# ADR1399_BURN-IN_TOOL.net
KiCad netlist of a schematic drawn in Altium Designer
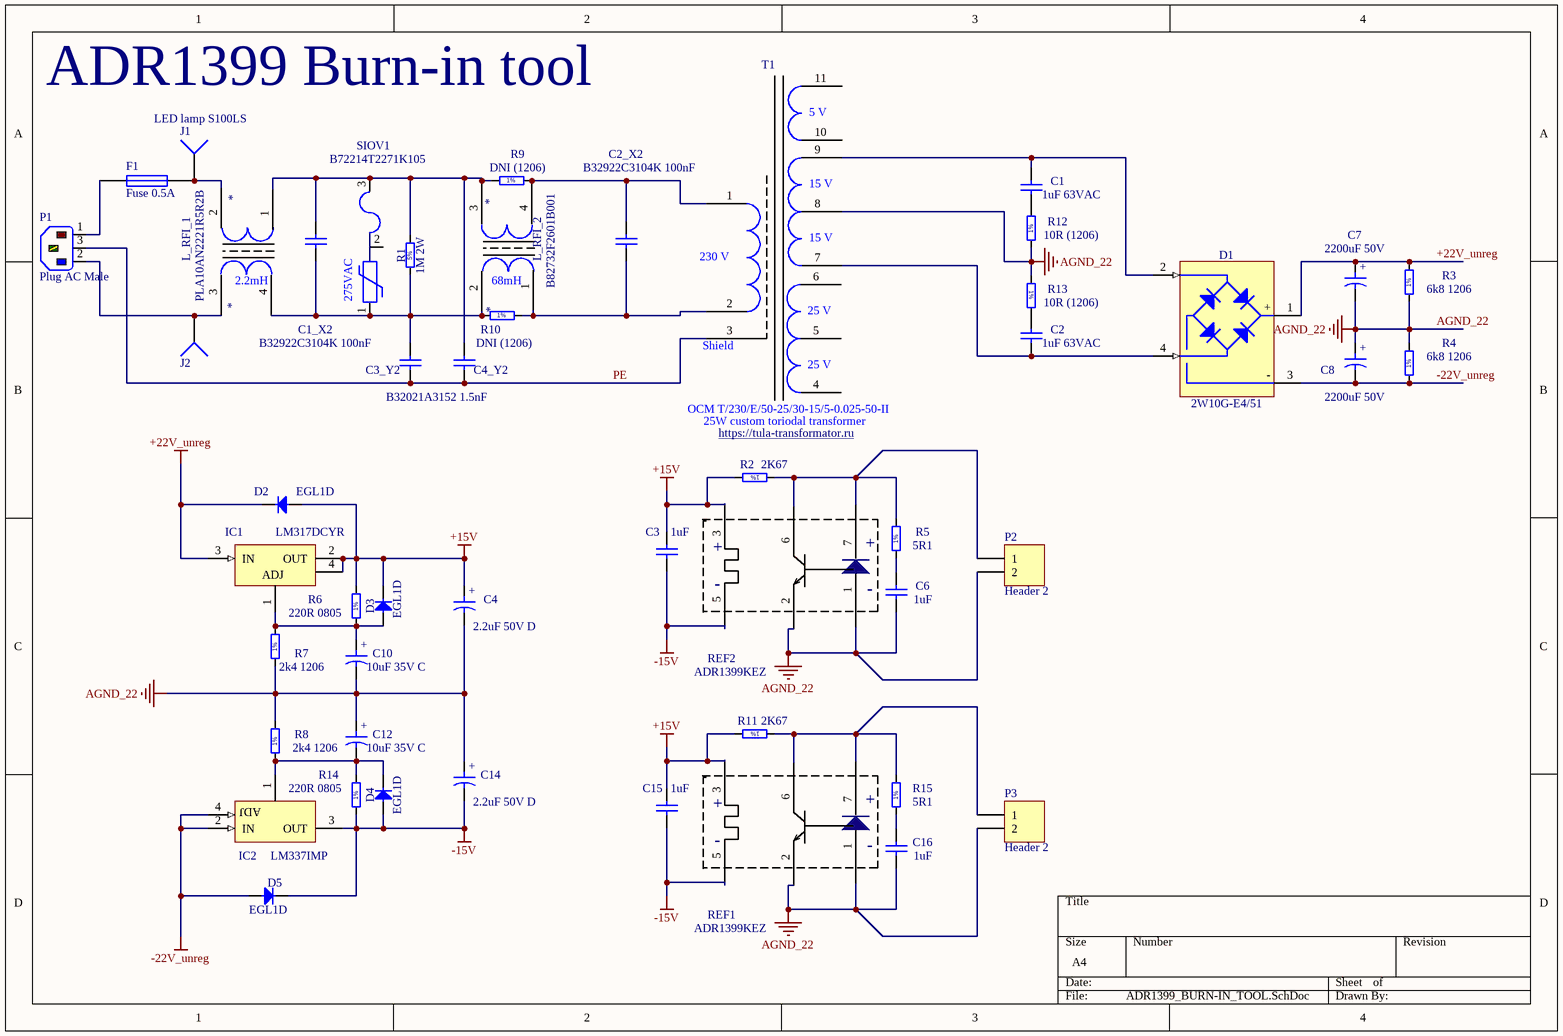
[diagram p0: ADR1399_BURN-IN_TOOL.SchDoc]

(export (version "E")
  (design (tool "Eeschema 10.0.6"))
  (components
    (comp (ref "C1")
      (value "1uF 63VAC")
      (footprint "B32522C1105")
      (description "Non-polarised capacitor")
      (fields
        (field (name "PART NUMBER") "CPPR_330NF_630V_5%_2250-1050X2650X1650")
        (field (name "VOLTAGE") "630VDC/250VAC")
        (field (name "AUTHOR") "CERN DEM JLC")
      )
      (libsource (lib "Capacitors") (part "Capacitor - non polarized"))
    )
    (comp (ref "C1_X2")
      (value "B32922C3104K 100nF")
      (footprint "B32922D3334K")
      (description "Non-polarised capacitor")
      (fields
        (field (name "PART NUMBER") "CPPR_330NF_630V_5%_2250-1050X2650X1650")
        (field (name "VOLTAGE") "630VDC/250VAC")
        (field (name "AUTHOR") "CERN DEM JLC")
      )
      (libsource (lib "Capacitors") (part "Capacitor - non polarized"))
    )
    (comp (ref "C2")
      (value "1uF 63VAC")
      (footprint "B32522C1105")
      (description "Non-polarised capacitor")
      (fields
        (field (name "PART NUMBER") "CPPR_330NF_630V_5%_2250-1050X2650X1650")
        (field (name "VOLTAGE") "630VDC/250VAC")
        (field (name "AUTHOR") "CERN DEM JLC")
      )
      (libsource (lib "Capacitors") (part "Capacitor - non polarized"))
    )
    (comp (ref "C2_X2")
      (value "B32922C3104K 100nF")
      (footprint "B32922D3334K")
      (description "Non-polarised capacitor")
      (fields
        (field (name "PART NUMBER") "CPPR_330NF_630V_5%_2250-1050X2650X1650")
        (field (name "VOLTAGE") "630VDC/250VAC")
        (field (name "AUTHOR") "CERN DEM JLC")
      )
      (libsource (lib "Capacitors") (part "Capacitor - non polarized"))
    )
    (comp (ref "C3")
      (value "1uF")
      (footprint "C0805(2013)")
      (description "Non-polarised capacitor")
      (fields
        (field (name "PART NUMBER") "CC1206_1UF_25V_10%_X7R")
        (field (name "VOLTAGE") "25V")
        (field (name "AUTHOR") "CERN DEM JLC")
      )
      (libsource (lib "Capacitors") (part "Capacitor - non polarized"))
    )
    (comp (ref "C3_Y2")
      (value "B32021A3152 1.5nF")
      (footprint "B32021A3152")
      (description "Non-polarised capacitor")
      (fields
        (field (name "PART NUMBER") "CPPR_330NF_630V_5%_2250-1050X2650X1650")
        (field (name "VOLTAGE") "630VDC/250VAC")
        (field (name "AUTHOR") "CERN DEM JLC")
      )
      (libsource (lib "Capacitors") (part "Capacitor - non polarized"))
    )
    (comp (ref "C4")
      (value "2.2uF 50V D")
      (footprint "CAPMP7343X310N")
      (description "Polarised capacitor")
      (fields
        (field (name "PART NUMBER") "CTE7343-31_22UF_35V_20%_LESR0400")
        (field (name "VOLTAGE") "35V")
        (field (name "AUTHOR") "CERN DEM MR")
      )
      (libsource (lib "Capacitors") (part "Capacitor - polarized"))
    )
    (comp (ref "C4_Y2")
      (value "B32021A3152 1.5nF")
      (footprint "B32021A3152")
      (description "Non-polarised capacitor")
      (fields
        (field (name "PART NUMBER") "CPPR_330NF_630V_5%_2250-1050X2650X1650")
        (field (name "VOLTAGE") "630VDC/250VAC")
        (field (name "AUTHOR") "CERN DEM JLC")
      )
      (libsource (lib "Capacitors") (part "Capacitor - non polarized"))
    )
    (comp (ref "C6")
      (value "1uF")
      (footprint "C0805(2013)")
      (description "Non-polarised capacitor")
      (fields
        (field (name "PART NUMBER") "CC1206_1UF_25V_10%_X7R")
        (field (name "VOLTAGE") "25V")
        (field (name "AUTHOR") "CERN DEM JLC")
      )
      (libsource (lib "Capacitors") (part "Capacitor - non polarized"))
    )
    (comp (ref "C7")
      (value "2200uF 50V")
      (footprint "CAPPR750-1850X3750")
      (description "Polarised capacitor")
      (fields
        (field (name "PART NUMBER") "CAER_10000UF_16V_20%_CHEMI-CON_EKYB160ELL103MMP1S")
        (field (name "VOLTAGE") "16V")
        (field (name "AUTHOR") "CERN DEM JLC")
      )
      (libsource (lib "Capacitors") (part "Capacitor - polarized"))
    )
    (comp (ref "C8")
      (value "2200uF 50V")
      (footprint "CAPPR750-1850X3750")
      (description "Polarised capacitor")
      (fields
        (field (name "PART NUMBER") "CAER_10000UF_16V_20%_CHEMI-CON_EKYB160ELL103MMP1S")
        (field (name "VOLTAGE") "16V")
        (field (name "AUTHOR") "CERN DEM JLC")
      )
      (libsource (lib "Capacitors") (part "Capacitor - polarized"))
    )
    (comp (ref "C10")
      (value "10uF 35V C")
      (footprint "CAPMP6032X280N")
      (description "Polarised capacitor")
      (fields
        (field (name "PART NUMBER") "CTE6032-28_10UF_25V_10%_LESR0500")
        (field (name "VOLTAGE") "25V")
        (field (name "AUTHOR") "CERN DEM JLC")
      )
      (libsource (lib "Capacitors") (part "Capacitor - polarized"))
    )
    (comp (ref "C12")
      (value "10uF 35V C")
      (footprint "CAPMP6032X280N")
      (description "Polarised capacitor")
      (fields
        (field (name "PART NUMBER") "CTE6032-28_10UF_25V_10%_LESR0500")
        (field (name "VOLTAGE") "25V")
        (field (name "AUTHOR") "CERN DEM JLC")
      )
      (libsource (lib "Capacitors") (part "Capacitor - polarized"))
    )
    (comp (ref "C14")
      (value "2.2uF 50V D")
      (footprint "CAPMP7343X310N")
      (description "Polarised capacitor")
      (fields
        (field (name "PART NUMBER") "CTE7343-31_22UF_35V_20%_LESR0400")
        (field (name "VOLTAGE") "35V")
        (field (name "AUTHOR") "CERN DEM MR")
      )
      (libsource (lib "Capacitors") (part "Capacitor - polarized"))
    )
    (comp (ref "C15")
      (value "1uF")
      (footprint "C0805(2013)")
      (description "Non-polarised capacitor")
      (fields
        (field (name "PART NUMBER") "CC1206_1UF_25V_10%_X7R")
        (field (name "VOLTAGE") "25V")
        (field (name "AUTHOR") "CERN DEM JLC")
      )
      (libsource (lib "Capacitors") (part "Capacitor - non polarized"))
    )
    (comp (ref "C16")
      (value "1uF")
      (footprint "C0805(2013)")
      (description "Non-polarised capacitor")
      (fields
        (field (name "PART NUMBER") "CC1206_1UF_25V_10%_X7R")
        (field (name "VOLTAGE") "25V")
        (field (name "AUTHOR") "CERN DEM JLC")
      )
      (libsource (lib "Capacitors") (part "Capacitor - non polarized"))
    )
    (comp (ref "D1")
      (value "2W10G-E4/51")
      (footprint "VISHAY_WOG")
      (description "Bridge Rectifier 1+ 2AC 3- 4AC")
      (fields
        (field (name "PART NUMBER") "W005G-E4/51")
        (field (name "VOLTAGE") "50V")
        (field (name "AUTHOR") "CERN DEM JLC")
      )
      (libsource (lib "ICs And Semiconductors") (part "Bridge Rectifier 1+ 2AC 3- 4AC"))
    )
    (comp (ref "D2")
      (value "EGL1D")
      (footprint "DIOMELF3515N")
      (description "Diode")
      (fields
        (field (name "PART NUMBER") "PMLL4148L")
        (field (name "VOLTAGE") "75V")
        (field (name "AUTHOR") "CERN DEM JLC")
      )
      (libsource (lib "ICs And Semiconductors") (part "Diode"))
    )
    (comp (ref "D3")
      (value "EGL1D")
      (footprint "DIOMELF3515N")
      (description "Diode")
      (fields
        (field (name "PART NUMBER") "PMLL4148L")
        (field (name "VOLTAGE") "75V")
        (field (name "AUTHOR") "CERN DEM JLC")
      )
      (libsource (lib "ICs And Semiconductors") (part "Diode"))
    )
    (comp (ref "D4")
      (value "EGL1D")
      (footprint "DIOMELF3515N")
      (description "Diode")
      (fields
        (field (name "PART NUMBER") "PMLL4148L")
        (field (name "VOLTAGE") "75V")
        (field (name "AUTHOR") "CERN DEM JLC")
      )
      (libsource (lib "ICs And Semiconductors") (part "Diode"))
    )
    (comp (ref "D5")
      (value "EGL1D")
      (footprint "DIOMELF3515N")
      (description "Diode")
      (fields
        (field (name "PART NUMBER") "PMLL4148L")
        (field (name "VOLTAGE") "75V")
        (field (name "AUTHOR") "CERN DEM JLC")
      )
      (libsource (lib "ICs And Semiconductors") (part "Diode"))
    )
    (comp (ref "F1")
      (value "Fuse 0.5A")
      (footprint "FUSE")
      (description "Fuse")
      (fields (field (name "PUBLISHER") "Altium Limited"))
      (libsource (lib "Miscellaneous Devices") (part "Fuse 1"))
    )
    (comp (ref "IC1")
      (value "LM317DCYR")
      (footprint "SOT230P700X180-4N")
      (description "3-Terminal Regulator 1=Adj 2=OUT 3=IN 4=OUT")
      (fields
        (field (name "PART NUMBER") "LM317EMP")
        (field (name "MANUFACTURER") "TEXAS INSTRUMENTS")
        (field (name "AUTHOR") "CERN DEM JLC")
      )
      (libsource (lib "ICs And Semiconductors") (part "REG3+1 1ADJ-2OUT-3IN+4OUT"))
    )
    (comp (ref "IC2")
      (value "LM337IMP")
      (footprint "SOT230P700X180-4N")
      (description "3-Terminal Regulator 1=Adj 2=IN 3=OUT 4=IN")
      (fields
        (field (name "PART NUMBER") "LM337IMP/NOPB")
        (field (name "MANUFACTURER") "TEXAS INSTRUMENTS")
        (field (name "AUTHOR") "CERN DEM JLC")
      )
      (libsource (lib "ICs And Semiconductors") (part "REG3+1 1ADJ-2IN-3OUT+4IN"))
    )
    (comp (ref "J1")
      (value "Socket")
      (footprint "PIN1")
      (fields (field (name "PUBLISHER") "Altium Limited"))
      (libsource (lib "Miscellaneous Connectors") (part "Socket"))
    )
    (comp (ref "J2")
      (value "Socket")
      (footprint "PIN1")
      (fields (field (name "PUBLISHER") "Altium Limited"))
      (libsource (lib "Miscellaneous Connectors") (part "Socket"))
    )
    (comp (ref "L_RFI_1")
      (value "PLA10AN2221R5R2B")
      (footprint "PLA10AN2221R5R2B")
      (libsource (lib "My SCH library") (part "PLA10AN2221R5R2B"))
    )
    (comp (ref "L_RFI_2")
      (value "B82732F2601B001")
      (footprint "B82732F")
      (libsource (lib "") (part "PLA10AN2221R5R2B_1"))
    )
    (comp (ref "P1")
      (value "Plug AC Male")
      (footprint "AS-205")
      (description "IEC Mains Power Inlet, EN60 320-1 C14 Class I Cold Condition, PC Flange Rear Mount, Chassis Plug")
      (fields (field (name "PUBLISHER") "Altium Limited"))
      (libsource (lib "Miscellaneous Connectors") (part "Plug AC Male"))
    )
    (comp (ref "P2")
      (value "Header 2")
      (footprint "HDR1X2")
      (description "Header, 2-Pin")
      (fields (field (name "PUBLISHER") "Altium Limited"))
      (libsource (lib "Miscellaneous Connectors") (part "Header 2"))
    )
    (comp (ref "P3")
      (value "Header 2")
      (footprint "HDR1X2")
      (description "Header, 2-Pin")
      (fields (field (name "PUBLISHER") "Altium Limited"))
      (libsource (lib "Miscellaneous Connectors") (part "Header 2"))
    )
    (comp (ref "R1")
      (value "1M 2W")
      (footprint "RES_TYCO_CFR200")
      (description "Resistor - 5%")
      (fields
        (field (name "PART NUMBER") "RCF_NO-VALUE_5%_2W_0-450PPM_TYCO_CFR200")
        (field (name "POWER") "2W")
        (field (name "AUTHOR") "CERN DEM JLC")
      )
      (libsource (lib "Resistors") (part "Resistor - 5%"))
    )
    (comp (ref "R2")
      (value "2K67")
      (footprint "R0603-1%")
      (description "Resistor - 1%")
      (fields
        (field (name "PART NUMBER") "R1206_5R6_1%_0.25W_200PPM")
        (field (name "POWER") "0.25W")
        (field (name "AUTHOR") "CERN DEM JLC")
      )
      (libsource (lib "Resistors") (part "Resistor - 1%"))
    )
    (comp (ref "R3")
      (value "6k8 1206")
      (footprint "RESC3216X65N")
      (description "Resistor - 1%")
      (fields
        (field (name "PART NUMBER") "R1206_2K4_1%_0.25W_100PPM")
        (field (name "POWER") "0.25W")
        (field (name "AUTHOR") "CERN DEM JLC")
      )
      (libsource (lib "Resistors") (part "Resistor - 1%"))
    )
    (comp (ref "R4")
      (value "6k8 1206")
      (footprint "RESC3216X65N")
      (description "Resistor - 1%")
      (fields
        (field (name "PART NUMBER") "R1206_2K4_1%_0.25W_100PPM")
        (field (name "POWER") "0.25W")
        (field (name "AUTHOR") "CERN DEM JLC")
      )
      (libsource (lib "Resistors") (part "Resistor - 1%"))
    )
    (comp (ref "R5")
      (value "5R1")
      (footprint "R0603-1%")
      (description "Resistor - 1%")
      (fields
        (field (name "PART NUMBER") "R1206_5R6_1%_0.25W_200PPM")
        (field (name "POWER") "0.25W")
        (field (name "AUTHOR") "CERN DEM JLC")
      )
      (libsource (lib "Resistors") (part "Resistor - 1%"))
    )
    (comp (ref "R6")
      (value "220R 0805")
      (footprint "RESC2012X60N")
      (description "Resistor - 1%")
      (fields
        (field (name "PART NUMBER") "R0805_220R_1%_0.125W_100PPM")
        (field (name "POWER") "0.125W")
        (field (name "AUTHOR") "CERN DEM JLC")
      )
      (libsource (lib "Resistors") (part "Resistor - 1%"))
    )
    (comp (ref "R7")
      (value "2k4 1206")
      (footprint "RESC3216X65N")
      (description "Resistor - 1%")
      (fields
        (field (name "PART NUMBER") "R1206_2K4_1%_0.25W_100PPM")
        (field (name "POWER") "0.25W")
        (field (name "AUTHOR") "CERN DEM JLC")
      )
      (libsource (lib "Resistors") (part "Resistor - 1%"))
    )
    (comp (ref "R8")
      (value "2k4 1206")
      (footprint "RESC3216X65N")
      (description "Resistor - 1%")
      (fields
        (field (name "PART NUMBER") "R1206_2K4_1%_0.25W_100PPM")
        (field (name "POWER") "0.25W")
        (field (name "AUTHOR") "CERN DEM JLC")
      )
      (libsource (lib "Resistors") (part "Resistor - 1%"))
    )
    (comp (ref "R9")
      (value "DNI (1206)")
      (footprint "RESC3216X65N")
      (description "Resistor - 1%")
      (fields
        (field (name "PART NUMBER") "R1206_2K4_1%_0.25W_100PPM")
        (field (name "POWER") "0.25W")
        (field (name "AUTHOR") "CERN DEM JLC")
      )
      (libsource (lib "Resistors") (part "Resistor - 1%"))
    )
    (comp (ref "R10")
      (value "DNI (1206)")
      (footprint "RESC3216X65N")
      (description "Resistor - 1%")
      (fields
        (field (name "PART NUMBER") "R1206_2K4_1%_0.25W_100PPM")
        (field (name "POWER") "0.25W")
        (field (name "AUTHOR") "CERN DEM JLC")
      )
      (libsource (lib "Resistors") (part "Resistor - 1%"))
    )
    (comp (ref "R11")
      (value "2K67")
      (footprint "R0603-1%")
      (description "Resistor - 1%")
      (fields
        (field (name "PART NUMBER") "R1206_5R6_1%_0.25W_200PPM")
        (field (name "POWER") "0.25W")
        (field (name "AUTHOR") "CERN DEM JLC")
      )
      (libsource (lib "Resistors") (part "Resistor - 1%"))
    )
    (comp (ref "R12")
      (value "10R (1206)")
      (footprint "RESC3216X65N")
      (description "Resistor - 1%")
      (fields
        (field (name "PART NUMBER") "R1206_2K4_1%_0.25W_100PPM")
        (field (name "POWER") "0.25W")
        (field (name "AUTHOR") "CERN DEM JLC")
      )
      (libsource (lib "Resistors") (part "Resistor - 1%"))
    )
    (comp (ref "R13")
      (value "10R (1206)")
      (footprint "RESC3216X65N")
      (description "Resistor - 1%")
      (fields
        (field (name "PART NUMBER") "R1206_2K4_1%_0.25W_100PPM")
        (field (name "POWER") "0.25W")
        (field (name "AUTHOR") "CERN DEM JLC")
      )
      (libsource (lib "Resistors") (part "Resistor - 1%"))
    )
    (comp (ref "R14")
      (value "220R 0805")
      (footprint "RESC2012X60N")
      (description "Resistor - 1%")
      (fields
        (field (name "PART NUMBER") "R0805_220R_1%_0.125W_100PPM")
        (field (name "POWER") "0.125W")
        (field (name "AUTHOR") "CERN DEM JLC")
      )
      (libsource (lib "Resistors") (part "Resistor - 1%"))
    )
    (comp (ref "R15")
      (value "5R1")
      (footprint "R0603-1%")
      (description "Resistor - 1%")
      (fields
        (field (name "PART NUMBER") "R1206_5R6_1%_0.25W_200PPM")
        (field (name "POWER") "0.25W")
        (field (name "AUTHOR") "CERN DEM JLC")
      )
      (libsource (lib "Resistors") (part "Resistor - 1%"))
    )
    (comp (ref "REF1")
      (value "ADR1399KEZ")
      (footprint "LCC-8 socket")
      (libsource (lib "My SCH library") (part "ADR1399KEZ"))
    )
    (comp (ref "REF2")
      (value "ADR1399KEZ")
      (footprint "LCC-8 socket")
      (libsource (lib "My SCH library") (part "ADR1399KEZ"))
    )
    (comp (ref "SIOV1")
      (value "B72214T2271K105")
      (footprint "B72214T2271K105")
      (fields (field (name "ORDER") "B72214T2271K105") (field (name "PUBLISHER") "Altium Limited"))
      (libsource (lib "My SCH library") (part "B72214T2271K105"))
    )
    (comp (ref "T1")
      (value "OCM T/230/E/50-25/30-15/5-0.025-50-II")
      (footprint "OCM T/230/E/50-25/30-15/5-0.025-50-II")
      (libsource (lib "My SCH library") (part "OCM T/230/E/50-25/30-15/5-0.025-50-II"))
    )
  )
  (nets
    (net (code "1") (name "+15V") (class "Default")
      (node (ref "C15") (pin "2") (pinfunction "2_2") (pintype "passive"))
      (node (ref "C3") (pin "2") (pinfunction "2_2") (pintype "passive"))
      (node (ref "C4") (pin "1") (pinfunction "1_1") (pintype "passive"))
      (node (ref "D2") (pin "2") (pinfunction "A_2") (pintype "passive"))
      (node (ref "D3") (pin "1") (pinfunction "C_1") (pintype "passive"))
      (node (ref "IC1") (pin "2") (pinfunction "OUT_2") (pintype "power_in"))
      (node (ref "IC1") (pin "4") (pinfunction "OUT_4") (pintype "power_in"))
      (node (ref "R11") (pin "2") (pinfunction "2_2") (pintype "passive"))
      (node (ref "R2") (pin "2") (pinfunction "2_2") (pintype "passive"))
      (node (ref "R6") (pin "2") (pinfunction "2_2") (pintype "passive"))
      (node (ref "REF1") (pin "3") (pinfunction "3_3") (pintype "passive"))
      (node (ref "REF2") (pin "3") (pinfunction "3_3") (pintype "passive"))
    )
    (net (code "2") (name "+22V_unreg") (class "Default")
      (node (ref "C7") (pin "1") (pinfunction "1_1") (pintype "passive"))
      (node (ref "D1") (pin "1") (pinfunction "+_1") (pintype "power_in"))
      (node (ref "D2") (pin "1") (pinfunction "C_1") (pintype "passive"))
      (node (ref "IC1") (pin "3") (pinfunction "IN_3") (pintype "input"))
      (node (ref "R3") (pin "2") (pinfunction "2_2") (pintype "passive"))
    )
    (net (code "3") (name "-15V") (class "Default")
      (node (ref "C14") (pin "2") (pinfunction "2_2") (pintype "passive"))
      (node (ref "C15") (pin "1") (pinfunction "1_1") (pintype "passive"))
      (node (ref "C3") (pin "1") (pinfunction "1_1") (pintype "passive"))
      (node (ref "D4") (pin "2") (pinfunction "A_2") (pintype "passive"))
      (node (ref "D5") (pin "1") (pinfunction "C_1") (pintype "passive"))
      (node (ref "IC2") (pin "3") (pinfunction "OUT_3") (pintype "power_in"))
      (node (ref "R14") (pin "1") (pinfunction "1_1") (pintype "passive"))
      (node (ref "REF1") (pin "5") (pinfunction "5_5") (pintype "passive"))
      (node (ref "REF2") (pin "5") (pinfunction "5_5") (pintype "passive"))
    )
    (net (code "4") (name "-22V_unreg") (class "Default")
      (node (ref "C8") (pin "2") (pinfunction "2_2") (pintype "passive"))
      (node (ref "D1") (pin "3") (pinfunction "-_3") (pintype "power_in"))
      (node (ref "D5") (pin "2") (pinfunction "A_2") (pintype "passive"))
      (node (ref "IC2") (pin "2") (pinfunction "IN_2") (pintype "input"))
      (node (ref "IC2") (pin "4") (pinfunction "IN_4") (pintype "input"))
      (node (ref "R4") (pin "1") (pinfunction "1_1") (pintype "passive"))
    )
    (net (code "5") (name "/PE") (class "Default")
      (node (ref "C3_Y2") (pin "1") (pinfunction "1_1") (pintype "passive"))
      (node (ref "C4_Y2") (pin "1") (pinfunction "1_1") (pintype "passive"))
      (node (ref "P1") (pin "3") (pinfunction "E_3") (pintype "power_in"))
      (node (ref "T1") (pin "3") (pinfunction "3_3") (pintype "passive"))
    )
    (net (code "6") (name "AGND_22") (class "Default")
      (node (ref "C10") (pin "2") (pinfunction "2_2") (pintype "passive"))
      (node (ref "C12") (pin "1") (pinfunction "1_1") (pintype "passive"))
      (node (ref "C14") (pin "1") (pinfunction "1_1") (pintype "passive"))
      (node (ref "C16") (pin "1") (pinfunction "1_1") (pintype "passive"))
      (node (ref "C4") (pin "2") (pinfunction "2_2") (pintype "passive"))
      (node (ref "C6") (pin "1") (pinfunction "1_1") (pintype "passive"))
      (node (ref "C7") (pin "2") (pinfunction "2_2") (pintype "passive"))
      (node (ref "C8") (pin "1") (pinfunction "1_1") (pintype "passive"))
      (node (ref "P2") (pin "2") (pinfunction "2_2") (pintype "passive"))
      (node (ref "P3") (pin "2") (pinfunction "2_2") (pintype "passive"))
      (node (ref "R12") (pin "1") (pinfunction "1_1") (pintype "passive"))
      (node (ref "R13") (pin "1") (pinfunction "1_1") (pintype "passive"))
      (node (ref "R3") (pin "1") (pinfunction "1_1") (pintype "passive"))
      (node (ref "R4") (pin "2") (pinfunction "2_2") (pintype "passive"))
      (node (ref "R7") (pin "1") (pinfunction "1_1") (pintype "passive"))
      (node (ref "R8") (pin "2") (pinfunction "2_2") (pintype "passive"))
      (node (ref "REF1") (pin "1") (pinfunction "1_1") (pintype "passive"))
      (node (ref "REF1") (pin "2") (pinfunction "2_2") (pintype "passive"))
      (node (ref "REF2") (pin "1") (pinfunction "1_1") (pintype "passive"))
      (node (ref "REF2") (pin "2") (pinfunction "2_2") (pintype "passive"))
      (node (ref "T1") (pin "8") (pinfunction "8_8") (pintype "passive"))
    )
    (net (code "7") (name "Net-(C1-Pad1)") (class "Default")
      (node (ref "C1") (pin "1") (pinfunction "1_1") (pintype "passive"))
      (node (ref "R12") (pin "2") (pinfunction "2_2") (pintype "passive"))
    )
    (net (code "8") (name "Net-(C1-Pad2)") (class "Default")
      (node (ref "C1") (pin "2") (pinfunction "2_2") (pintype "passive"))
      (node (ref "D1") (pin "2") (pinfunction "AC_2") (pintype "input"))
      (node (ref "T1") (pin "9") (pinfunction "9_9") (pintype "passive"))
    )
    (net (code "9") (name "Net-(C1_X2-Pad1)") (class "Default")
      (node (ref "C1_X2") (pin "1") (pinfunction "1_1") (pintype "passive"))
      (node (ref "C3_Y2") (pin "2") (pinfunction "2_2") (pintype "passive"))
      (node (ref "L_RFI_1") (pin "4") (pinfunction "4_4") (pintype "passive"))
      (node (ref "L_RFI_2") (pin "2") (pinfunction "2_2") (pintype "passive"))
      (node (ref "R1") (pin "1") (pinfunction "1_1") (pintype "passive"))
      (node (ref "R10") (pin "1") (pinfunction "1_1") (pintype "passive"))
      (node (ref "SIOV1") (pin "1") (pinfunction "1_1") (pintype "passive"))
    )
    (net (code "10") (name "Net-(C1_X2-Pad2)") (class "Default")
      (node (ref "C1_X2") (pin "2") (pinfunction "2_2") (pintype "passive"))
      (node (ref "C4_Y2") (pin "2") (pinfunction "2_2") (pintype "passive"))
      (node (ref "L_RFI_1") (pin "1") (pinfunction "1_1") (pintype "passive"))
      (node (ref "L_RFI_2") (pin "3") (pinfunction "3_3") (pintype "passive"))
      (node (ref "R1") (pin "2") (pinfunction "2_2") (pintype "passive"))
      (node (ref "R9") (pin "1") (pinfunction "1_1") (pintype "passive"))
      (node (ref "SIOV1") (pin "3") (pinfunction "3_3") (pintype "passive"))
    )
    (net (code "11") (name "Net-(C2-Pad1)") (class "Default")
      (node (ref "C2") (pin "1") (pinfunction "1_1") (pintype "passive"))
      (node (ref "D1") (pin "4") (pinfunction "AC_4") (pintype "input"))
      (node (ref "T1") (pin "7") (pinfunction "8_7") (pintype "passive"))
    )
    (net (code "12") (name "Net-(C2-Pad2)") (class "Default")
      (node (ref "C2") (pin "2") (pinfunction "2_2") (pintype "passive"))
      (node (ref "R13") (pin "2") (pinfunction "2_2") (pintype "passive"))
    )
    (net (code "13") (name "Net-(C2_X2-Pad1)") (class "Default")
      (node (ref "C2_X2") (pin "1") (pinfunction "1_1") (pintype "passive"))
      (node (ref "L_RFI_2") (pin "1") (pinfunction "1_1") (pintype "passive"))
      (node (ref "R10") (pin "2") (pinfunction "2_2") (pintype "passive"))
      (node (ref "T1") (pin "2") (pintype "passive"))
    )
    (net (code "14") (name "Net-(C2_X2-Pad2)") (class "Default")
      (node (ref "C2_X2") (pin "2") (pinfunction "2_2") (pintype "passive"))
      (node (ref "L_RFI_2") (pin "4") (pinfunction "4_4") (pintype "passive"))
      (node (ref "R9") (pin "2") (pinfunction "2_2") (pintype "passive"))
      (node (ref "T1") (pin "1") (pinfunction "1_1") (pintype "passive"))
    )
    (net (code "15") (name "Net-(C6-Pad2)") (class "Default")
      (node (ref "C6") (pin "2") (pinfunction "2_2") (pintype "passive"))
      (node (ref "R5") (pin "1") (pinfunction "1_1") (pintype "passive"))
    )
    (net (code "16") (name "Net-(C16-Pad2)") (class "Default")
      (node (ref "C16") (pin "2") (pinfunction "2_2") (pintype "passive"))
      (node (ref "R15") (pin "1") (pinfunction "1_1") (pintype "passive"))
    )
    (net (code "17") (name "Net-(D3-A)") (class "Default")
      (node (ref "C10") (pin "1") (pinfunction "1_1") (pintype "passive"))
      (node (ref "D3") (pin "2") (pinfunction "A_2") (pintype "passive"))
      (node (ref "IC1") (pin "1") (pinfunction "ADJ_1") (pintype "power_in"))
      (node (ref "R6") (pin "1") (pinfunction "1_1") (pintype "passive"))
      (node (ref "R7") (pin "2") (pinfunction "2_2") (pintype "passive"))
    )
    (net (code "18") (name "Net-(D4-C)") (class "Default")
      (node (ref "C12") (pin "2") (pinfunction "2_2") (pintype "passive"))
      (node (ref "D4") (pin "1") (pinfunction "C_1") (pintype "passive"))
      (node (ref "IC2") (pin "1") (pinfunction "ADJ_1") (pintype "power_in"))
      (node (ref "R14") (pin "2") (pinfunction "2_2") (pintype "passive"))
      (node (ref "R8") (pin "1") (pinfunction "1_1") (pintype "passive"))
    )
    (net (code "19") (name "Net-(F1-Pad2)") (class "Default")
      (node (ref "F1") (pin "2") (pinfunction "2_2") (pintype "passive"))
      (node (ref "J1") (pin "1") (pinfunction "1_1") (pintype "passive"))
      (node (ref "L_RFI_1") (pin "2") (pinfunction "2_2") (pintype "passive"))
    )
    (net (code "20") (name "Net-(P1-L)") (class "Default")
      (node (ref "F1") (pin "1") (pinfunction "1_1") (pintype "passive"))
      (node (ref "P1") (pin "1") (pinfunction "L_1") (pintype "power_in"))
    )
    (net (code "21") (name "Net-(P1-N)") (class "Default")
      (node (ref "J2") (pin "1") (pinfunction "1_1") (pintype "passive"))
      (node (ref "L_RFI_1") (pin "3") (pinfunction "3_3") (pintype "passive"))
      (node (ref "P1") (pin "2") (pinfunction "N_2") (pintype "power_in"))
    )
    (net (code "22") (name "Net-(P2-Pad1)") (class "Default")
      (node (ref "P2") (pin "1") (pinfunction "1_1") (pintype "passive"))
      (node (ref "R2") (pin "1") (pinfunction "1_1") (pintype "passive"))
      (node (ref "R5") (pin "2") (pinfunction "2_2") (pintype "passive"))
      (node (ref "REF2") (pin "6") (pinfunction "6_6") (pintype "passive"))
      (node (ref "REF2") (pin "7") (pinfunction "7_7") (pintype "passive"))
    )
    (net (code "23") (name "Net-(P3-Pad1)") (class "Default")
      (node (ref "P3") (pin "1") (pinfunction "1_1") (pintype "passive"))
      (node (ref "R11") (pin "1") (pinfunction "1_1") (pintype "passive"))
      (node (ref "R15") (pin "2") (pinfunction "2_2") (pintype "passive"))
      (node (ref "REF1") (pin "6") (pinfunction "6_6") (pintype "passive"))
      (node (ref "REF1") (pin "7") (pinfunction "7_7") (pintype "passive"))
    )
    (net (code "24") (name "unconnected-(SIOV1-Pad2)") (class "Default")
      (node (ref "SIOV1") (pin "2") (pinfunction "2_2") (pintype "passive"))
    )
    (net (code "25") (name "unconnected-(T1-5-Pad10)") (class "Default")
      (node (ref "T1") (pin "10") (pinfunction "5_10") (pintype "passive"))
    )
    (net (code "26") (name "unconnected-(T1-Pad4)") (class "Default")
      (node (ref "T1") (pin "4") (pinfunction "4_4") (pintype "passive"))
    )
    (net (code "27") (name "unconnected-(T1-Pad5)") (class "Default")
      (node (ref "T1") (pin "5") (pinfunction "5_5") (pintype "passive"))
    )
    (net (code "28") (name "unconnected-(T1-Pad6)") (class "Default")
      (node (ref "T1") (pin "6") (pinfunction "6_6") (pintype "passive"))
    )
    (net (code "29") (name "unconnected-(T1-Pad11)") (class "Default")
      (node (ref "T1") (pin "11") (pinfunction "11_11") (pintype "passive"))
    )
  )
)
